# MCU_144_IOs.net
KiCad netlist of a schematic drawn in Altium Designer
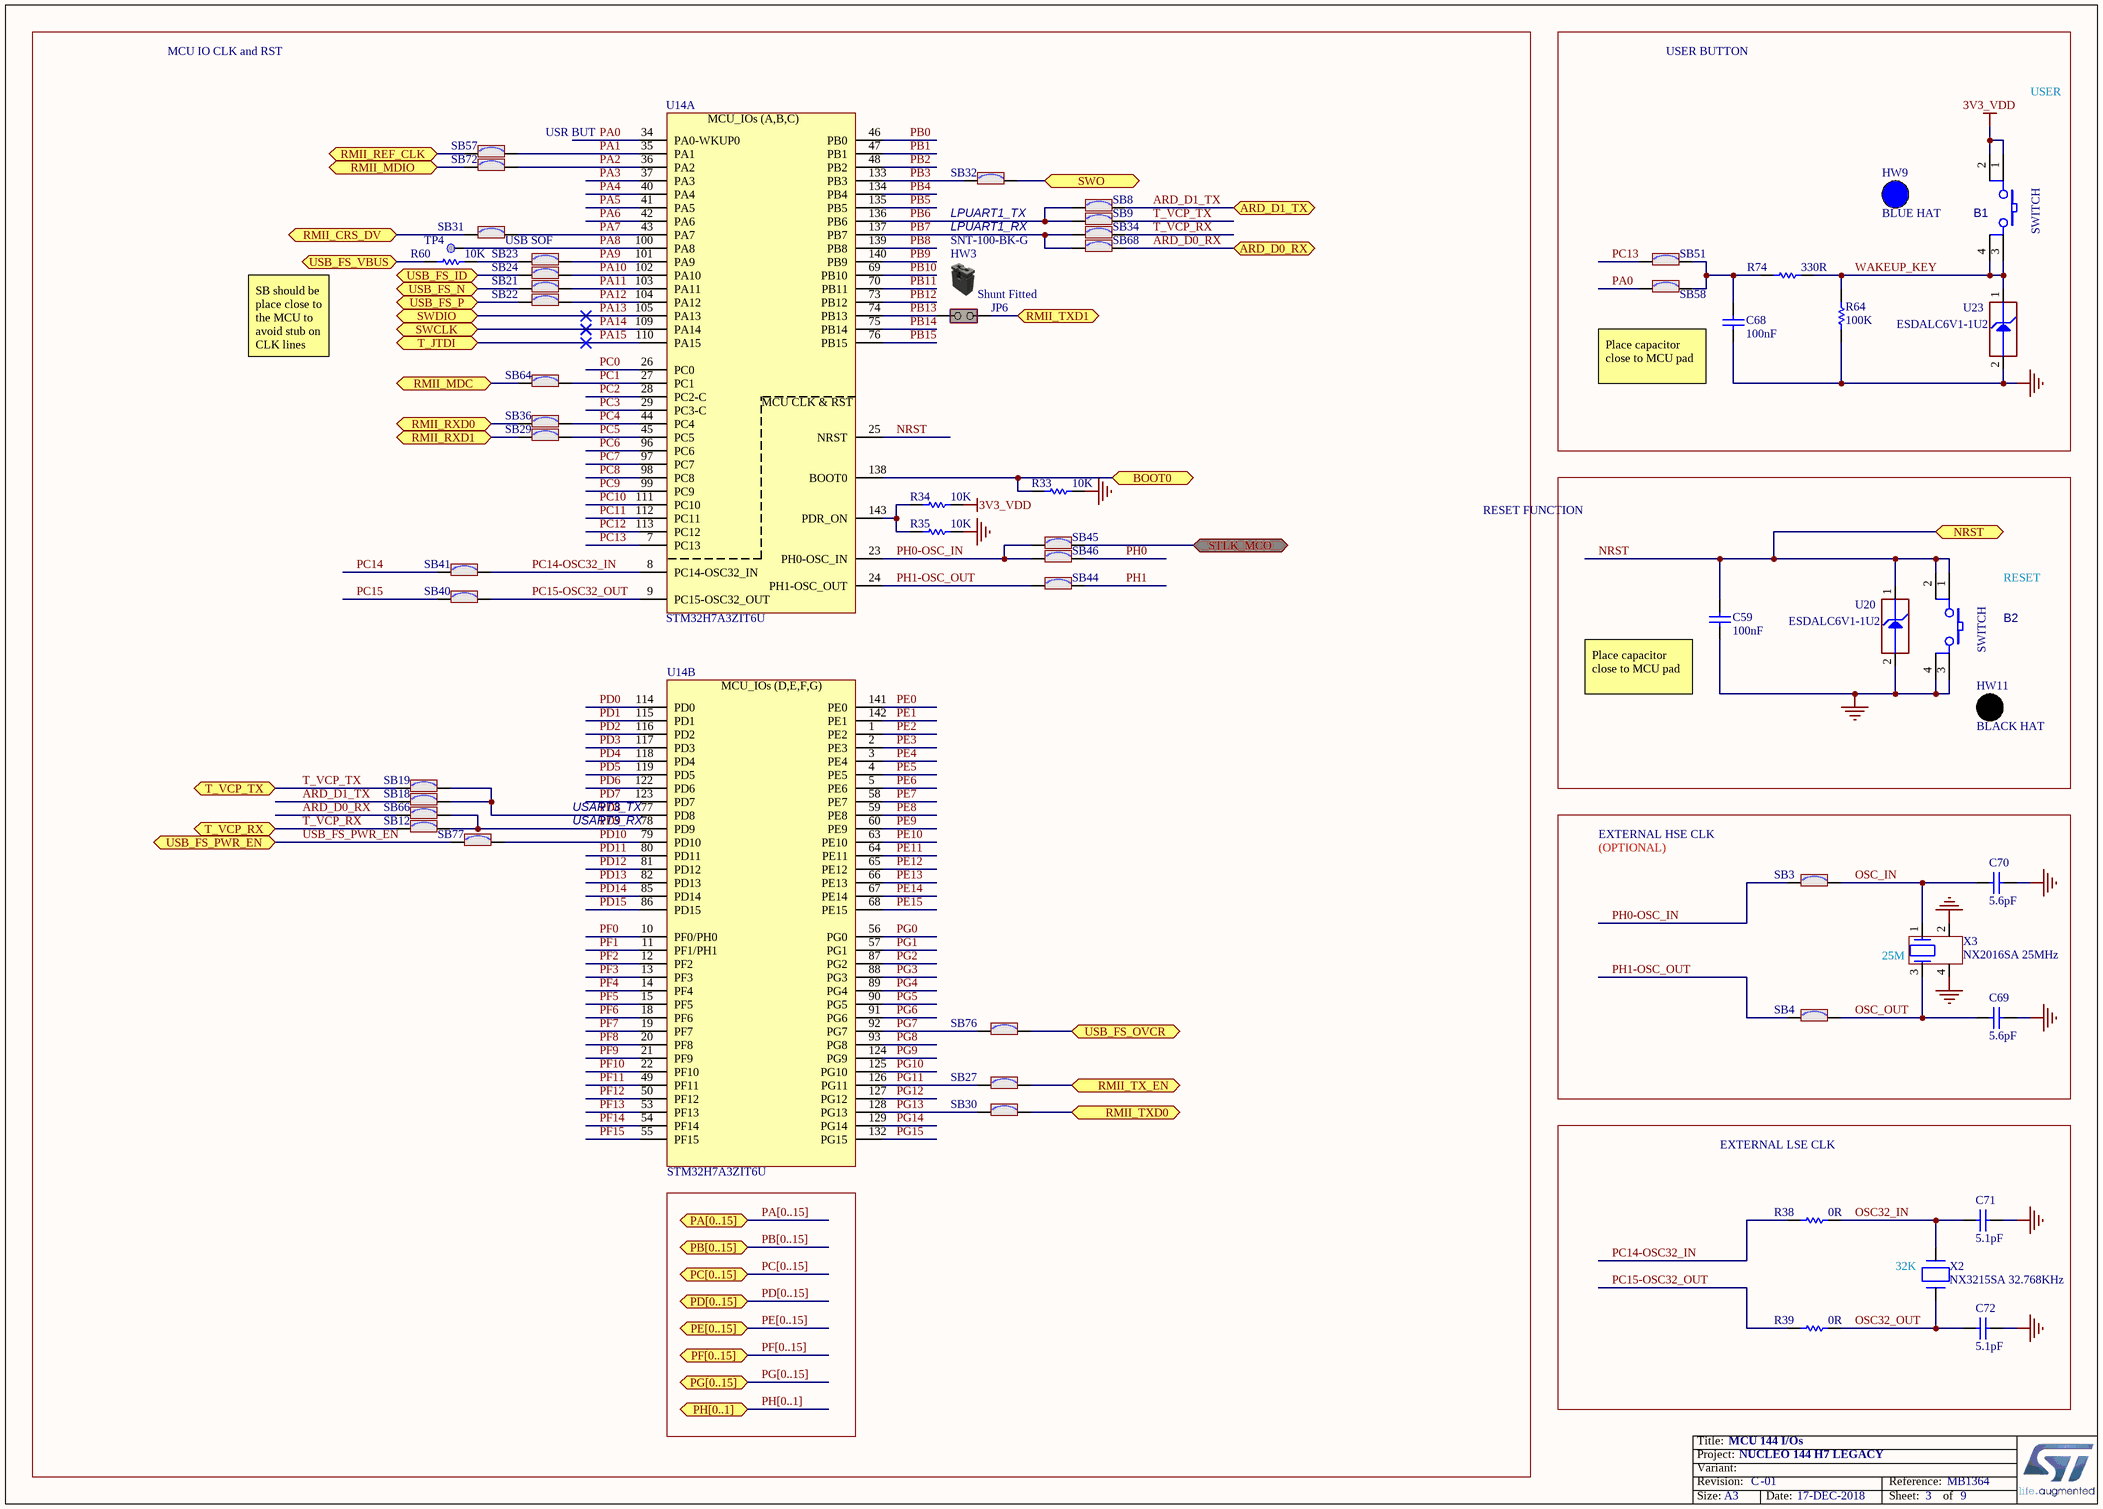
[diagram p0: MCU_144_IOs.SchDoc]

(export (version "E")
  (design (tool "Eeschema 10.0.6"))
  (components
    (comp (ref "B1")
      (value "SWITCH")
      (footprint "SWI_WEALTHMETAL_TD-0341_4P_BLUE")
      (description "Non-Open Push-Button 0.1A 24V")
      (fields
        (field (name "INTERNAL_PART_NUMBER") "MCD-00002")
        (field (name "MANUFACTURER_PART_NUMBER") "TD-0341")
        (field (name "PROVIDED_BY") "SUBCO")
      )
      (libsource (lib "MCD_PARTS_database") (part "SW-PUSH-CMS"))
    )
    (comp (ref "B2")
      (value "SWITCH")
      (footprint "SWI_WEALTHMETAL_TD-0341_4P_BLACK")
      (description "Non-Open Push-Button 0.1A 24V BLACK")
      (fields
        (field (name "INTERNAL_PART_NUMBER") "MCD-00001")
        (field (name "MANUFACTURER_PART_NUMBER") "TD-0341")
        (field (name "PROVIDED_BY") "SUBCO")
      )
      (libsource (lib "MCD_PARTS_database") (part "SW-PUSH-CMS"))
    )
    (comp (ref "C59")
      (value "100nF")
      (footprint "C0603")
      (description "Capacitor, MLCC, 100nF, 6V3, X5R, 10%, 0603, T=0,8mm")
      (fields
        (field (name "INTERNAL_PART_NUMBER") "MCD-00237")
        (field (name "MANUFACTURER_PART_NUMBER") "CC0603KRX5R5BB104")
        (field (name "PROVIDED_BY") "SUBCO")
      )
      (libsource (lib "MCD_PARTS_database") (part "Capacitor"))
    )
    (comp (ref "C68")
      (value "100nF")
      (footprint "C0603")
      (description "Capacitor, MLCC, 100nF, 6V3, X5R, 10%, 0603, T=0,8mm")
      (fields
        (field (name "INTERNAL_PART_NUMBER") "MCD-00237")
        (field (name "MANUFACTURER_PART_NUMBER") "CC0603KRX5R5BB104")
        (field (name "PROVIDED_BY") "SUBCO")
      )
      (libsource (lib "MCD_PARTS_database") (part "Capacitor"))
    )
    (comp (ref "C69")
      (value "5.6pF")
      (footprint "C0402")
      (description "Capacitor, MLCC, 5.6pF, 50V, NPO, 5%, 0402, T=0,5mm")
      (fields
        (field (name "INTERNAL_PART_NUMBER") "MCD-01374")
        (field (name "MANUFACTURER_PART_NUMBER") "CC0402BRNPO9BN5R6")
        (field (name "PROVIDED_BY") "SUBCO")
      )
      (libsource (lib "MCD_PARTS_database") (part "Capacitor"))
    )
    (comp (ref "C70")
      (value "5.6pF")
      (footprint "C0402")
      (description "Capacitor, MLCC, 5.6pF, 50V, NPO, 5%, 0402, T=0,5mm")
      (fields
        (field (name "INTERNAL_PART_NUMBER") "MCD-01374")
        (field (name "MANUFACTURER_PART_NUMBER") "CC0402BRNPO9BN5R6")
        (field (name "PROVIDED_BY") "SUBCO")
      )
      (libsource (lib "MCD_PARTS_database") (part "Capacitor"))
    )
    (comp (ref "C71")
      (value "5.1pF")
      (footprint "C0402")
      (description "Capacitor, MLCC, 5.1pF, 50V, NPO, +-0.25pF, 0402, T=0.5mm")
      (fields
        (field (name "INTERNAL_PART_NUMBER") "MCD-00003")
        (field (name "MANUFACTURER_PART_NUMBER") "CC0402CRNPO9BN5R1")
        (field (name "PROVIDED_BY") "SUBCO")
      )
      (libsource (lib "MCD_PARTS_database") (part "Capacitor"))
    )
    (comp (ref "C72")
      (value "5.1pF")
      (footprint "C0402")
      (description "Capacitor, MLCC, 5.1pF, 50V, NPO, +-0.25pF, 0402, T=0.5mm")
      (fields
        (field (name "INTERNAL_PART_NUMBER") "MCD-00003")
        (field (name "MANUFACTURER_PART_NUMBER") "CC0402CRNPO9BN5R1")
        (field (name "PROVIDED_BY") "SUBCO")
      )
      (libsource (lib "MCD_PARTS_database") (part "Capacitor"))
    )
    (comp (ref "HW3")
      (value "SNT-100-BK-G")
      (description "SHUNT 2.54mm BLACK")
      (fields
        (field (name "INTERNAL_PART_NUMBER") "MCD-00043")
        (field (name "MANUFACTURER") "SAMTEC")
        (field (name "PROVIDED_BY") "SUBCO")
      )
      (libsource (lib "MCD_PARTS_database") (part "Shunt Black 2.54mm"))
    )
    (comp (ref "HW9")
      (value "BLUE HAT")
      (description "Blue Hat for switch TD0341X-G01-BLU")
      (fields
        (field (name "INTERNAL_PART_NUMBER") "MCD-00634")
        (field (name "MANUFACTURER_PART_NUMBER") "988.16.09.3.00002_SH-517")
        (field (name "PROVIDED_BY") "SUBCO")
      )
      (libsource (lib "MCD_PARTS_database") (part "BUTTON_HAT_BLUE"))
    )
    (comp (ref "HW11")
      (value "BLACK HAT")
      (description "Black Hat for switch TD0341X-G01-BLA")
      (fields
        (field (name "INTERNAL_PART_NUMBER") "MCD-00635")
        (field (name "MANUFACTURER_PART_NUMBER") "988.16.09.3.00003_SH-517")
        (field (name "PROVIDED_BY") "SUBCO")
      )
      (libsource (lib "MCD_PARTS_database") (part "BUTTON_HAT_BLACK"))
    )
    (comp (ref "JP6")
      (value "Shunt Fitted")
      (footprint "CON_SAMTEC_TSW-102-07-G-S")
      (description "Header, 2x1, 2,54mm, VR, TH, Height 5.84mm/2.54mm - Shunt Fitted by default")
      (fields
        (field (name "INTERNAL_PART_NUMBER") "MCD-00683")
        (field (name "MANUFACTURER_PART_NUMBER") "TSW-102-07-x-S")
        (field (name "PROVIDED_BY") "SUBCO")
      )
      (libsource (lib "MCD_PARTS_database") (part "Jumper_Header 2x1 Fitted"))
    )
    (comp (ref "R33")
      (value "10K")
      (footprint "R0603")
      (description "Resistor,10K,0603,1%,1/10W")
      (fields
        (field (name "INTERNAL_PART_NUMBER") "MCD-00220")
        (field (name "MANUFACTURER_PART_NUMBER") "RC0603FR-0710KL")
        (field (name "PROVIDED_BY") "SUBCO")
      )
      (libsource (lib "MCD_PARTS_database") (part "Resistor"))
    )
    (comp (ref "R34")
      (value "10K")
      (footprint "R0603")
      (description "Resistor,10K,0603,1%,1/10W")
      (fields
        (field (name "INTERNAL_PART_NUMBER") "MCD-00220")
        (field (name "MANUFACTURER_PART_NUMBER") "RC0603FR-0710KL")
        (field (name "PROVIDED_BY") "SUBCO")
      )
      (libsource (lib "MCD_PARTS_database") (part "Resistor"))
    )
    (comp (ref "R35")
      (value "10K")
      (footprint "R0603")
      (description "Resistor,10K,0603,1%,1/10W")
      (fields
        (field (name "INTERNAL_PART_NUMBER") "MCD-00220")
        (field (name "MANUFACTURER_PART_NUMBER") "RC0603FR-0710KL")
        (field (name "PROVIDED_BY") "SUBCO")
      )
      (libsource (lib "MCD_PARTS_database") (part "Resistor"))
    )
    (comp (ref "R38")
      (value "0R")
      (footprint "R0603")
      (description "Resistor,0R,0603,5%,1/10W")
      (fields
        (field (name "INTERNAL_PART_NUMBER") "MCD-00056")
        (field (name "MANUFACTURER_PART_NUMBER") "RC0603JR-070RL")
        (field (name "PROVIDED_BY") "SUBCO")
      )
      (libsource (lib "MCD_PARTS_database") (part "Resistor"))
    )
    (comp (ref "R39")
      (value "0R")
      (footprint "R0603")
      (description "Resistor,0R,0603,5%,1/10W")
      (fields
        (field (name "INTERNAL_PART_NUMBER") "MCD-00056")
        (field (name "MANUFACTURER_PART_NUMBER") "RC0603JR-070RL")
        (field (name "PROVIDED_BY") "SUBCO")
      )
      (libsource (lib "MCD_PARTS_database") (part "Resistor"))
    )
    (comp (ref "R60")
      (value "10K")
      (footprint "R0402")
      (description "Resistor,10K,0402,1%,1/16W")
      (fields
        (field (name "INTERNAL_PART_NUMBER") "MCD-00053")
        (field (name "MANUFACTURER_PART_NUMBER") "RC0402FR-0710KL")
        (field (name "PROVIDED_BY") "SUBCO")
      )
      (libsource (lib "MCD_PARTS_database") (part "Resistor"))
    )
    (comp (ref "R64")
      (value "100K")
      (footprint "R0603")
      (description "Resistor,100K,0603,1%,1/10W")
      (fields
        (field (name "INTERNAL_PART_NUMBER") "MCD-00223")
        (field (name "MANUFACTURER_PART_NUMBER") "RC0603FR-07100KL")
        (field (name "PROVIDED_BY") "SUBCO")
      )
      (libsource (lib "MCD_PARTS_database") (part "Resistor"))
    )
    (comp (ref "R74")
      (value "330R")
      (footprint "R0603")
      (description "Resistor,330R,0603,1%,1/10W")
      (fields
        (field (name "INTERNAL_PART_NUMBER") "MCD-00197")
        (field (name "MANUFACTURER_PART_NUMBER") "RC0603FR-07330RL")
        (field (name "PROVIDED_BY") "SUBCO")
      )
      (libsource (lib "MCD_PARTS_database") (part "Resistor"))
    )
    (comp (ref "SB3")
      (value "SB_ON")
      (footprint "SOLDER-BRIDGE_R0603-0R")
      (description "Solder Bridge ON")
      (fields
        (field (name "INTERNAL_PART_NUMBER") "MCD-00071")
        (field (name "MANUFACTURER_PART_NUMBER") "RC0603JR-070RL")
        (field (name "PROVIDED_BY") "SUBCO")
      )
      (libsource (lib "MCD_PARTS_database") (part "SB_ON"))
    )
    (comp (ref "SB4")
      (value "SB_ON")
      (footprint "SOLDER-BRIDGE_R0603-0R")
      (description "Solder Bridge ON")
      (fields
        (field (name "INTERNAL_PART_NUMBER") "MCD-00071")
        (field (name "MANUFACTURER_PART_NUMBER") "RC0603JR-070RL")
        (field (name "PROVIDED_BY") "SUBCO")
      )
      (libsource (lib "MCD_PARTS_database") (part "SB_ON"))
    )
    (comp (ref "SB8")
      (value "SB_ON")
      (footprint "SOLDER-BRIDGE_R0603-0R")
      (description "Solder Bridge ON")
      (fields
        (field (name "INTERNAL_PART_NUMBER") "MCD-00071")
        (field (name "MANUFACTURER_PART_NUMBER") "RC0603JR-070RL")
        (field (name "PROVIDED_BY") "SUBCO")
      )
      (libsource (lib "") (part "SB_ON_1"))
    )
    (comp (ref "SB9")
      (value "SB_ON")
      (footprint "SOLDER-BRIDGE_R0603-0R")
      (description "Solder Bridge ON")
      (fields
        (field (name "INTERNAL_PART_NUMBER") "MCD-00071")
        (field (name "MANUFACTURER_PART_NUMBER") "RC0603JR-070RL")
        (field (name "PROVIDED_BY") "SUBCO")
      )
      (libsource (lib "") (part "SB_ON_1"))
    )
    (comp (ref "SB12")
      (value "SB_ON")
      (footprint "SOLDER-BRIDGE_R0603-0R")
      (description "Solder Bridge ON")
      (fields
        (field (name "INTERNAL_PART_NUMBER") "MCD-00071")
        (field (name "MANUFACTURER_PART_NUMBER") "RC0603JR-070RL")
        (field (name "PROVIDED_BY") "SUBCO")
      )
      (libsource (lib "") (part "SB_ON_1"))
    )
    (comp (ref "SB18")
      (value "SB_ON")
      (footprint "SOLDER-BRIDGE_R0603-0R")
      (description "Solder Bridge ON")
      (fields
        (field (name "INTERNAL_PART_NUMBER") "MCD-00071")
        (field (name "MANUFACTURER_PART_NUMBER") "RC0603JR-070RL")
        (field (name "PROVIDED_BY") "SUBCO")
      )
      (libsource (lib "") (part "SB_ON_1"))
    )
    (comp (ref "SB19")
      (value "SB_ON")
      (footprint "SOLDER-BRIDGE_R0603-0R")
      (description "Solder Bridge ON")
      (fields
        (field (name "INTERNAL_PART_NUMBER") "MCD-00071")
        (field (name "MANUFACTURER_PART_NUMBER") "RC0603JR-070RL")
        (field (name "PROVIDED_BY") "SUBCO")
      )
      (libsource (lib "") (part "SB_ON_1"))
    )
    (comp (ref "SB21")
      (value "SB_ON")
      (footprint "SOLDER-BRIDGE_R0603-0R")
      (description "Solder Bridge ON")
      (fields
        (field (name "INTERNAL_PART_NUMBER") "MCD-00071")
        (field (name "MANUFACTURER_PART_NUMBER") "RC0603JR-070RL")
        (field (name "PROVIDED_BY") "SUBCO")
      )
      (libsource (lib "") (part "SB_ON_1"))
    )
    (comp (ref "SB22")
      (value "SB_ON")
      (footprint "SOLDER-BRIDGE_R0603-0R")
      (description "Solder Bridge ON")
      (fields
        (field (name "INTERNAL_PART_NUMBER") "MCD-00071")
        (field (name "MANUFACTURER_PART_NUMBER") "RC0603JR-070RL")
        (field (name "PROVIDED_BY") "SUBCO")
      )
      (libsource (lib "") (part "SB_ON_1"))
    )
    (comp (ref "SB23")
      (value "SB_ON")
      (footprint "SOLDER-BRIDGE_R0603-0R")
      (description "Solder Bridge ON")
      (fields
        (field (name "INTERNAL_PART_NUMBER") "MCD-00071")
        (field (name "MANUFACTURER_PART_NUMBER") "RC0603JR-070RL")
        (field (name "PROVIDED_BY") "SUBCO")
      )
      (libsource (lib "") (part "SB_ON_1"))
    )
    (comp (ref "SB24")
      (value "SB_ON")
      (footprint "SOLDER-BRIDGE_R0603-0R")
      (description "Solder Bridge ON")
      (fields
        (field (name "INTERNAL_PART_NUMBER") "MCD-00071")
        (field (name "MANUFACTURER_PART_NUMBER") "RC0603JR-070RL")
        (field (name "PROVIDED_BY") "SUBCO")
      )
      (libsource (lib "") (part "SB_ON_1"))
    )
    (comp (ref "SB27")
      (value "SB_ON")
      (footprint "SOLDER-BRIDGE_R0603-0R")
      (description "Solder Bridge ON")
      (fields
        (field (name "INTERNAL_PART_NUMBER") "MCD-00071")
        (field (name "MANUFACTURER_PART_NUMBER") "RC0603JR-070RL")
        (field (name "PROVIDED_BY") "SUBCO")
      )
      (libsource (lib "") (part "SB_ON_1"))
    )
    (comp (ref "SB29")
      (value "SB_ON")
      (footprint "SOLDER-BRIDGE_R0603-0R")
      (description "Solder Bridge ON")
      (fields
        (field (name "INTERNAL_PART_NUMBER") "MCD-00071")
        (field (name "MANUFACTURER_PART_NUMBER") "RC0603JR-070RL")
        (field (name "PROVIDED_BY") "SUBCO")
      )
      (libsource (lib "MCD_PARTS_database") (part "SB_ON"))
    )
    (comp (ref "SB30")
      (value "SB_ON")
      (footprint "SOLDER-BRIDGE_R0603-0R")
      (description "Solder Bridge ON")
      (fields
        (field (name "INTERNAL_PART_NUMBER") "MCD-00071")
        (field (name "MANUFACTURER_PART_NUMBER") "RC0603JR-070RL")
        (field (name "PROVIDED_BY") "SUBCO")
      )
      (libsource (lib "") (part "SB_ON_1"))
    )
    (comp (ref "SB31")
      (value "SB_ON")
      (footprint "SOLDER-BRIDGE_R0603-0R")
      (description "Solder Bridge ON")
      (fields
        (field (name "INTERNAL_PART_NUMBER") "MCD-00071")
        (field (name "MANUFACTURER_PART_NUMBER") "RC0603JR-070RL")
        (field (name "PROVIDED_BY") "SUBCO")
      )
      (libsource (lib "") (part "SB_ON_1"))
    )
    (comp (ref "SB32")
      (value "SB_ON")
      (footprint "SOLDER-BRIDGE_R0603-0R")
      (description "Solder Bridge ON")
      (fields
        (field (name "INTERNAL_PART_NUMBER") "MCD-00071")
        (field (name "MANUFACTURER_PART_NUMBER") "RC0603JR-070RL")
        (field (name "PROVIDED_BY") "SUBCO")
      )
      (libsource (lib "") (part "SB_ON_1"))
    )
    (comp (ref "SB34")
      (value "SB_ON")
      (footprint "SOLDER-BRIDGE_R0603-0R")
      (description "Solder Bridge ON")
      (fields
        (field (name "INTERNAL_PART_NUMBER") "MCD-00071")
        (field (name "MANUFACTURER_PART_NUMBER") "RC0603JR-070RL")
        (field (name "PROVIDED_BY") "SUBCO")
      )
      (libsource (lib "") (part "SB_ON_1"))
    )
    (comp (ref "SB36")
      (value "SB_ON")
      (footprint "SOLDER-BRIDGE_R0603-0R")
      (description "Solder Bridge ON")
      (fields
        (field (name "INTERNAL_PART_NUMBER") "MCD-00071")
        (field (name "MANUFACTURER_PART_NUMBER") "RC0603JR-070RL")
        (field (name "PROVIDED_BY") "SUBCO")
      )
      (libsource (lib "MCD_PARTS_database") (part "SB_ON"))
    )
    (comp (ref "SB40")
      (value "SB_ON")
      (footprint "SOLDER-BRIDGE_R0603-0R")
      (description "Solder Bridge ON")
      (fields
        (field (name "INTERNAL_PART_NUMBER") "MCD-00071")
        (field (name "MANUFACTURER_PART_NUMBER") "RC0603JR-070RL")
        (field (name "PROVIDED_BY") "SUBCO")
      )
      (libsource (lib "MCD_PARTS_database") (part "SB_ON"))
    )
    (comp (ref "SB41")
      (value "SB_ON")
      (footprint "SOLDER-BRIDGE_R0603-0R")
      (description "Solder Bridge ON")
      (fields
        (field (name "INTERNAL_PART_NUMBER") "MCD-00071")
        (field (name "MANUFACTURER_PART_NUMBER") "RC0603JR-070RL")
        (field (name "PROVIDED_BY") "SUBCO")
      )
      (libsource (lib "MCD_PARTS_database") (part "SB_ON"))
    )
    (comp (ref "SB44")
      (value "SB_ON")
      (footprint "SOLDER-BRIDGE_R0603-0R")
      (description "Solder Bridge ON")
      (fields
        (field (name "INTERNAL_PART_NUMBER") "MCD-00071")
        (field (name "MANUFACTURER_PART_NUMBER") "RC0603JR-070RL")
        (field (name "PROVIDED_BY") "SUBCO")
      )
      (libsource (lib "MCD_PARTS_database") (part "SB_ON"))
    )
    (comp (ref "SB45")
      (value "SB_ON")
      (footprint "SOLDER-BRIDGE_R0603-0R")
      (description "Solder Bridge ON")
      (fields
        (field (name "INTERNAL_PART_NUMBER") "MCD-00071")
        (field (name "MANUFACTURER_PART_NUMBER") "RC0603JR-070RL")
        (field (name "PROVIDED_BY") "SUBCO")
      )
      (libsource (lib "MCD_PARTS_database") (part "SB_ON"))
    )
    (comp (ref "SB46")
      (value "SB_ON")
      (footprint "SOLDER-BRIDGE_R0603-0R")
      (description "Solder Bridge ON")
      (fields
        (field (name "INTERNAL_PART_NUMBER") "MCD-00071")
        (field (name "MANUFACTURER_PART_NUMBER") "RC0603JR-070RL")
        (field (name "PROVIDED_BY") "SUBCO")
      )
      (libsource (lib "MCD_PARTS_database") (part "SB_ON"))
    )
    (comp (ref "SB51")
      (value "SB_ON")
      (footprint "SOLDER-BRIDGE_R0603-0R")
      (description "Solder Bridge ON")
      (fields
        (field (name "INTERNAL_PART_NUMBER") "MCD-00071")
        (field (name "MANUFACTURER_PART_NUMBER") "RC0603JR-070RL")
        (field (name "PROVIDED_BY") "SUBCO")
      )
      (libsource (lib "") (part "SB_ON_1"))
    )
    (comp (ref "SB57")
      (value "SB_ON")
      (footprint "SOLDER-BRIDGE_R0603-0R")
      (description "Solder Bridge ON")
      (fields
        (field (name "INTERNAL_PART_NUMBER") "MCD-00071")
        (field (name "MANUFACTURER_PART_NUMBER") "RC0603JR-070RL")
        (field (name "PROVIDED_BY") "SUBCO")
      )
      (libsource (lib "") (part "SB_ON_1"))
    )
    (comp (ref "SB58")
      (value "SB_ON")
      (footprint "SOLDER-BRIDGE_R0603-0R")
      (description "Solder Bridge ON")
      (fields
        (field (name "INTERNAL_PART_NUMBER") "MCD-00071")
        (field (name "MANUFACTURER_PART_NUMBER") "RC0603JR-070RL")
        (field (name "PROVIDED_BY") "SUBCO")
      )
      (libsource (lib "") (part "SB_ON_1"))
    )
    (comp (ref "SB64")
      (value "SB_ON")
      (footprint "SOLDER-BRIDGE_R0603-0R")
      (description "Solder Bridge ON")
      (fields
        (field (name "INTERNAL_PART_NUMBER") "MCD-00071")
        (field (name "MANUFACTURER_PART_NUMBER") "RC0603JR-070RL")
        (field (name "PROVIDED_BY") "SUBCO")
      )
      (libsource (lib "MCD_PARTS_database") (part "SB_ON"))
    )
    (comp (ref "SB66")
      (value "SB_ON")
      (footprint "SOLDER-BRIDGE_R0402-0R")
      (description "Solder Bridge 0402 ON")
      (fields
        (field (name "INTERNAL_PART_NUMBER") "MCD-01618")
        (field (name "MANUFACTURER_PART_NUMBER") "RC0402JR-070RL")
        (field (name "PROVIDED_BY") "SUBCO")
      )
      (libsource (lib "MCD_PARTS_database") (part "SB_ON"))
    )
    (comp (ref "SB68")
      (value "SB_ON")
      (footprint "SOLDER-BRIDGE_R0402-0R")
      (description "Solder Bridge 0402 ON")
      (fields
        (field (name "INTERNAL_PART_NUMBER") "MCD-01618")
        (field (name "MANUFACTURER_PART_NUMBER") "RC0402JR-070RL")
        (field (name "PROVIDED_BY") "SUBCO")
      )
      (libsource (lib "MCD_PARTS_database") (part "SB_ON"))
    )
    (comp (ref "SB72")
      (value "SB_ON")
      (footprint "SOLDER-BRIDGE_R0603-0R")
      (description "Solder Bridge ON")
      (fields
        (field (name "INTERNAL_PART_NUMBER") "MCD-00071")
        (field (name "MANUFACTURER_PART_NUMBER") "RC0603JR-070RL")
        (field (name "PROVIDED_BY") "SUBCO")
      )
      (libsource (lib "") (part "SB_ON_1"))
    )
    (comp (ref "SB76")
      (value "SB_ON")
      (footprint "SOLDER-BRIDGE_R0603-0R")
      (description "Solder Bridge ON")
      (fields
        (field (name "INTERNAL_PART_NUMBER") "MCD-00071")
        (field (name "MANUFACTURER_PART_NUMBER") "RC0603JR-070RL")
        (field (name "PROVIDED_BY") "SUBCO")
      )
      (libsource (lib "") (part "SB_ON_1"))
    )
    (comp (ref "SB77")
      (value "SB_ON")
      (footprint "SOLDER-BRIDGE_R0603-0R")
      (description "Solder Bridge ON")
      (fields
        (field (name "INTERNAL_PART_NUMBER") "MCD-00071")
        (field (name "MANUFACTURER_PART_NUMBER") "RC0603JR-070RL")
        (field (name "PROVIDED_BY") "SUBCO")
      )
      (libsource (lib "") (part "SB_ON_1"))
    )
    (comp (ref "TP4")
      (value "Test Point")
      (footprint "TP_SMD_1MM")
      (description "Test Point 1mm")
      (fields
        (field (name "INTERNAL_PART_NUMBER") "MCD-00074")
        (field (name "MANUFACTURER_PART_NUMBER") "n/a")
      )
      (libsource (lib "MCD_PARTS_database") (part "Test Point"))
    )
    (comp (ref "U14")
      (value "STM32H7A3ZIT6U")
      (footprint "ICC_LQFP144_20X20_P050_SOCKET_YAMAICHI_IC149-144-145-B5_NM")
      (description "STM32H7A3ZIT6U, LQFP144 package, 20x20")
      (fields
        (field (name "INTERNAL_PART_NUMBER") "MCD-01349")
        (field (name "MANUFACTURER") "STMICROELECTRONICS")
        (field (name "PROVIDED_BY") "SUBCO with ST control")
      )
      (libsource (lib "MCD_PARTS_database") (part "STM32H7A3ZIT6"))
    )
    (comp (ref "U20")
      (value "ESDALC6V1-1U2")
      (footprint "ESD_ST0201")
      (description "ESD protection 6V1")
      (fields
        (field (name "INTERNAL_PART_NUMBER") "MCD-00170")
        (field (name "MANUFACTURER") "STMICROELECTRONICS")
        (field (name "PROVIDED_BY") "SUBCO with ST control")
      )
      (libsource (lib "MCD_PARTS_database") (part "ESD-TRANSIL"))
    )
    (comp (ref "U23")
      (value "ESDALC6V1-1U2")
      (footprint "ESD_ST0201")
      (description "ESD protection 6V1")
      (fields
        (field (name "INTERNAL_PART_NUMBER") "MCD-00170")
        (field (name "MANUFACTURER") "STMICROELECTRONICS")
        (field (name "PROVIDED_BY") "SUBCO with ST control")
      )
      (libsource (lib "MCD_PARTS_database") (part "ESD-TRANSIL"))
    )
    (comp (ref "X2")
      (value "NX3215SA 32.768KHz")
      (footprint "CRY_NX3215SA_2P")
      (description "Crystal 32.768kHz, 6pF, +-20ppm, 50Kohms max, SMD")
      (fields
        (field (name "INTERNAL_PART_NUMBER") "MCD-00091")
        (field (name "MANUFACTURER_PART_NUMBER") "NX3215SA 32.768KHz EXS00A-MU00525")
        (field (name "PROVIDED_BY") "SUBCO")
      )
      (libsource (lib "MCD_PARTS_database") (part "XTAL_2_PINS"))
    )
    (comp (ref "X3")
      (value "NX2016SA 25MHz")
      (footprint "CRY_NX2016SA_4P")
      (description "Crystal 25MHz, 6pF, +-20ppm, 80ohms max, SMD")
      (fields
        (field (name "INTERNAL_PART_NUMBER") "MCD-01364")
        (field (name "MANUFACTURER_PART_NUMBER") "NX2016SA 25MHz EXS00A-CS11321")
        (field (name "PROVIDED_BY") "SUBCO")
      )
      (libsource (lib "MCD_PARTS_database") (part "XTAL_4_PINS"))
    )
  )
  (nets
    (net (code "1") (name "/ARD_D0_RX") (class "Default")
      (node (ref "SB66") (pin "1") (pinfunction "1_1") (pintype "passive"))
      (node (ref "SB68") (pin "2") (pinfunction "2_2") (pintype "passive"))
    )
    (net (code "2") (name "/ARD_D1_TX") (class "Default")
      (node (ref "SB18") (pin "2") (pinfunction "2_2") (pintype "passive"))
      (node (ref "SB8") (pin "1") (pinfunction "1_1") (pintype "passive"))
    )
    (net (code "3") (name "/BOOT0") (class "Default")
      (node (ref "R33") (pin "1") (pinfunction "1_1") (pintype "passive"))
      (node (ref "U14") (pin "138") (pinfunction "BOOT0_138") (pintype "passive"))
    )
    (net (code "4") (name "/NRST") (class "Default")
      (node (ref "B2") (pin "1") (pinfunction "1_1") (pintype "passive"))
      (node (ref "B2") (pin "2") (pinfunction "2_2") (pintype "passive"))
      (node (ref "C59") (pin "2") (pinfunction "2_2") (pintype "passive"))
      (node (ref "U14") (pin "25") (pinfunction "NRST_25") (pintype "passive"))
      (node (ref "U20") (pin "1") (pinfunction "IO1_1") (pintype "passive"))
    )
    (net (code "5") (name "/OSC32_IN") (class "Default")
      (node (ref "C71") (pin "1") (pinfunction "1_1") (pintype "passive"))
      (node (ref "R38") (pin "2") (pinfunction "2_2") (pintype "passive"))
      (node (ref "X2") (pin "2") (pinfunction "X2_2") (pintype "passive"))
    )
    (net (code "6") (name "/OSC32_OUT") (class "Default")
      (node (ref "C72") (pin "1") (pinfunction "1_1") (pintype "passive"))
      (node (ref "R39") (pin "2") (pinfunction "2_2") (pintype "passive"))
      (node (ref "X2") (pin "1") (pinfunction "X1_1") (pintype "passive"))
    )
    (net (code "7") (name "/OSC_IN") (class "Default")
      (node (ref "C70") (pin "1") (pinfunction "1_1") (pintype "passive"))
      (node (ref "SB3") (pin "2") (pinfunction "2_2") (pintype "passive"))
      (node (ref "X3") (pin "1") (pinfunction "1_1") (pintype "passive"))
    )
    (net (code "8") (name "/OSC_OUT") (class "Default")
      (node (ref "C69") (pin "1") (pinfunction "1_1") (pintype "passive"))
      (node (ref "SB4") (pin "2") (pinfunction "2_2") (pintype "passive"))
      (node (ref "X3") (pin "3") (pinfunction "3_3") (pintype "passive"))
    )
    (net (code "9") (name "/PA0") (class "Default")
      (node (ref "SB58") (pin "2") (pinfunction "2_2") (pintype "passive"))
      (node (ref "U14") (pin "34") (pinfunction "PA0-WKUP0_34") (pintype "passive"))
    )
    (net (code "10") (name "/PA1") (class "Default")
      (node (ref "SB57") (pin "1") (pinfunction "1_1") (pintype "passive"))
      (node (ref "U14") (pin "35") (pinfunction "PA1_35") (pintype "passive"))
    )
    (net (code "11") (name "/PA2") (class "Default")
      (node (ref "SB72") (pin "1") (pinfunction "1_1") (pintype "passive"))
      (node (ref "U14") (pin "36") (pinfunction "PA2_36") (pintype "passive"))
    )
    (net (code "12") (name "/PA3") (class "Default")
      (node (ref "U14") (pin "37") (pinfunction "PA3_37") (pintype "passive"))
    )
    (net (code "13") (name "/PA4") (class "Default")
      (node (ref "U14") (pin "40") (pinfunction "PA4_40") (pintype "passive"))
    )
    (net (code "14") (name "/PA5") (class "Default")
      (node (ref "U14") (pin "41") (pinfunction "PA5_41") (pintype "passive"))
    )
    (net (code "15") (name "/PA6") (class "Default")
      (node (ref "U14") (pin "42") (pinfunction "PA6_42") (pintype "passive"))
    )
    (net (code "16") (name "/PA7") (class "Default")
      (node (ref "SB31") (pin "1") (pinfunction "1_1") (pintype "passive"))
      (node (ref "U14") (pin "43") (pinfunction "PA7_43") (pintype "passive"))
    )
    (net (code "17") (name "/PA8") (class "Default")
      (node (ref "TP4") (pin "1") (pinfunction "1_1") (pintype "passive"))
      (node (ref "U14") (pin "100") (pinfunction "PA8_100") (pintype "passive"))
    )
    (net (code "18") (name "/PA9") (class "Default")
      (node (ref "SB23") (pin "1") (pinfunction "1_1") (pintype "passive"))
      (node (ref "U14") (pin "101") (pinfunction "PA9_101") (pintype "passive"))
    )
    (net (code "19") (name "/PA10") (class "Default")
      (node (ref "SB24") (pin "1") (pinfunction "1_1") (pintype "passive"))
      (node (ref "U14") (pin "102") (pinfunction "PA10_102") (pintype "passive"))
    )
    (net (code "20") (name "/PA11") (class "Default")
      (node (ref "SB21") (pin "1") (pinfunction "1_1") (pintype "passive"))
      (node (ref "U14") (pin "103") (pinfunction "PA11_103") (pintype "passive"))
    )
    (net (code "21") (name "/PA12") (class "Default")
      (node (ref "SB22") (pin "1") (pinfunction "1_1") (pintype "passive"))
      (node (ref "U14") (pin "104") (pinfunction "PA12_104") (pintype "passive"))
    )
    (net (code "22") (name "/PA13") (class "Default")
      (node (ref "U14") (pin "105") (pinfunction "PA13_105") (pintype "passive"))
    )
    (net (code "23") (name "/PA14") (class "Default")
      (node (ref "U14") (pin "109") (pinfunction "PA14_109") (pintype "passive"))
    )
    (net (code "24") (name "/PA15") (class "Default")
      (node (ref "U14") (pin "110") (pinfunction "PA15_110") (pintype "passive"))
    )
    (net (code "26") (name "/PB0") (class "Default")
      (node (ref "U14") (pin "46") (pinfunction "PB0_46") (pintype "passive"))
    )
    (net (code "27") (name "/PB1") (class "Default")
      (node (ref "U14") (pin "47") (pinfunction "PB1_47") (pintype "passive"))
    )
    (net (code "28") (name "/PB2") (class "Default")
      (node (ref "U14") (pin "48") (pinfunction "PB2_48") (pintype "passive"))
    )
    (net (code "29") (name "/PB3") (class "Default")
      (node (ref "SB32") (pin "2") (pinfunction "2_2") (pintype "passive"))
      (node (ref "U14") (pin "133") (pinfunction "PB3_133") (pintype "passive"))
    )
    (net (code "30") (name "/PB4") (class "Default")
      (node (ref "U14") (pin "134") (pinfunction "PB4_134") (pintype "passive"))
    )
    (net (code "31") (name "/PB5") (class "Default")
      (node (ref "U14") (pin "135") (pinfunction "PB5_135") (pintype "passive"))
    )
    (net (code "32") (name "/PB6") (class "Default")
      (node (ref "SB8") (pin "2") (pinfunction "2_2") (pintype "passive"))
      (node (ref "SB9") (pin "2") (pinfunction "2_2") (pintype "passive"))
      (node (ref "U14") (pin "136") (pinfunction "PB6_136") (pintype "passive"))
    )
    (net (code "33") (name "/PB7") (class "Default")
      (node (ref "SB34") (pin "2") (pinfunction "2_2") (pintype "passive"))
      (node (ref "SB68") (pin "1") (pinfunction "1_1") (pintype "passive"))
      (node (ref "U14") (pin "137") (pinfunction "PB7_137") (pintype "passive"))
    )
    (net (code "34") (name "/PB8") (class "Default")
      (node (ref "U14") (pin "139") (pinfunction "PB8_139") (pintype "passive"))
    )
    (net (code "35") (name "/PB9") (class "Default")
      (node (ref "U14") (pin "140") (pinfunction "PB9_140") (pintype "passive"))
    )
    (net (code "36") (name "/PB10") (class "Default")
      (node (ref "U14") (pin "69") (pinfunction "PB10_69") (pintype "passive"))
    )
    (net (code "37") (name "/PB11") (class "Default")
      (node (ref "U14") (pin "70") (pinfunction "PB11_70") (pintype "passive"))
    )
    (net (code "38") (name "/PB12") (class "Default")
      (node (ref "U14") (pin "73") (pinfunction "PB12_73") (pintype "passive"))
    )
    (net (code "39") (name "/PB13") (class "Default")
      (node (ref "JP6") (pin "1") (pinfunction "COMMON_1") (pintype "passive"))
      (node (ref "U14") (pin "74") (pinfunction "PB13_74") (pintype "passive"))
    )
    (net (code "40") (name "/PB14") (class "Default")
      (node (ref "U14") (pin "75") (pinfunction "PB14_75") (pintype "passive"))
    )
    (net (code "41") (name "/PB15") (class "Default")
      (node (ref "U14") (pin "76") (pinfunction "PB15_76") (pintype "passive"))
    )
    (net (code "43") (name "/PC0") (class "Default")
      (node (ref "U14") (pin "26") (pinfunction "PC0_26") (pintype "passive"))
    )
    (net (code "44") (name "/PC1") (class "Default")
      (node (ref "SB64") (pin "2") (pinfunction "2_2") (pintype "passive"))
      (node (ref "U14") (pin "27") (pinfunction "PC1_27") (pintype "passive"))
    )
    (net (code "45") (name "/PC2") (class "Default")
      (node (ref "U14") (pin "28") (pinfunction "PC2-C_28") (pintype "passive"))
    )
    (net (code "46") (name "/PC3") (class "Default")
      (node (ref "U14") (pin "29") (pinfunction "PC3-C_29") (pintype "passive"))
    )
    (net (code "47") (name "/PC4") (class "Default")
      (node (ref "SB36") (pin "2") (pinfunction "2_2") (pintype "passive"))
      (node (ref "U14") (pin "44") (pinfunction "PC4_44") (pintype "passive"))
    )
    (net (code "48") (name "/PC5") (class "Default")
      (node (ref "SB29") (pin "2") (pinfunction "2_2") (pintype "passive"))
      (node (ref "U14") (pin "45") (pinfunction "PC5_45") (pintype "passive"))
    )
    (net (code "49") (name "/PC6") (class "Default")
      (node (ref "U14") (pin "96") (pinfunction "PC6_96") (pintype "passive"))
    )
    (net (code "50") (name "/PC7") (class "Default")
      (node (ref "U14") (pin "97") (pinfunction "PC7_97") (pintype "passive"))
    )
    (net (code "51") (name "/PC8") (class "Default")
      (node (ref "U14") (pin "98") (pinfunction "PC8_98") (pintype "passive"))
    )
    (net (code "52") (name "/PC9") (class "Default")
      (node (ref "U14") (pin "99") (pinfunction "PC9_99") (pintype "passive"))
    )
    (net (code "53") (name "/PC10") (class "Default")
      (node (ref "U14") (pin "111") (pinfunction "PC10_111") (pintype "passive"))
    )
    (net (code "54") (name "/PC11") (class "Default")
      (node (ref "U14") (pin "112") (pinfunction "PC11_112") (pintype "passive"))
    )
    (net (code "55") (name "/PC12") (class "Default")
      (node (ref "U14") (pin "113") (pinfunction "PC12_113") (pintype "passive"))
    )
    (net (code "56") (name "/PC13") (class "Default")
      (node (ref "SB51") (pin "2") (pinfunction "2_2") (pintype "passive"))
      (node (ref "U14") (pin "7") (pinfunction "PC13_7") (pintype "passive"))
    )
    (net (code "57") (name "/PC14") (class "Default")
      (node (ref "SB41") (pin "1") (pinfunction "1_1") (pintype "passive"))
    )
    (net (code "58") (name "/PC14-OSC32_IN") (class "Default")
      (node (ref "R38") (pin "1") (pinfunction "1_1") (pintype "passive"))
      (node (ref "SB41") (pin "2") (pinfunction "2_2") (pintype "passive"))
      (node (ref "U14") (pin "8") (pinfunction "PC14-OSC32_IN_8") (pintype "passive"))
    )
    (net (code "59") (name "/PC15") (class "Default")
      (node (ref "SB40") (pin "1") (pinfunction "1_1") (pintype "passive"))
    )
    (net (code "60") (name "/PC15-OSC32_OUT") (class "Default")
      (node (ref "R39") (pin "1") (pinfunction "1_1") (pintype "passive"))
      (node (ref "SB40") (pin "2") (pinfunction "2_2") (pintype "passive"))
      (node (ref "U14") (pin "9") (pinfunction "PC15-OSC32_OUT_9") (pintype "passive"))
    )
    (net (code "62") (name "/PD0") (class "Default")
      (node (ref "U14") (pin "114") (pinfunction "PD0_114") (pintype "passive"))
    )
    (net (code "63") (name "/PD1") (class "Default")
      (node (ref "U14") (pin "115") (pinfunction "PD1_115") (pintype "passive"))
    )
    (net (code "64") (name "/PD2") (class "Default")
      (node (ref "U14") (pin "116") (pinfunction "PD2_116") (pintype "passive"))
    )
    (net (code "65") (name "/PD3") (class "Default")
      (node (ref "U14") (pin "117") (pinfunction "PD3_117") (pintype "passive"))
    )
    (net (code "66") (name "/PD4") (class "Default")
      (node (ref "U14") (pin "118") (pinfunction "PD4_118") (pintype "passive"))
    )
    (net (code "67") (name "/PD5") (class "Default")
      (node (ref "U14") (pin "119") (pinfunction "PD5_119") (pintype "passive"))
    )
    (net (code "68") (name "/PD6") (class "Default")
      (node (ref "U14") (pin "122") (pinfunction "PD6_122") (pintype "passive"))
    )
    (net (code "69") (name "/PD7") (class "Default")
      (node (ref "U14") (pin "123") (pinfunction "PD7_123") (pintype "passive"))
    )
    (net (code "70") (name "/PD8") (class "Default")
      (node (ref "SB18") (pin "1") (pinfunction "1_1") (pintype "passive"))
      (node (ref "SB19") (pin "1") (pinfunction "1_1") (pintype "passive"))
      (node (ref "U14") (pin "77") (pinfunction "PD8_77") (pintype "passive"))
    )
    (net (code "71") (name "/PD9") (class "Default")
      (node (ref "SB12") (pin "1") (pinfunction "1_1") (pintype "passive"))
      (node (ref "SB66") (pin "2") (pinfunction "2_2") (pintype "passive"))
      (node (ref "U14") (pin "78") (pinfunction "PD9_78") (pintype "passive"))
    )
    (net (code "72") (name "/PD10") (class "Default")
      (node (ref "SB77") (pin "1") (pinfunction "1_1") (pintype "passive"))
      (node (ref "U14") (pin "79") (pinfunction "PD10_79") (pintype "passive"))
    )
    (net (code "73") (name "/PD11") (class "Default")
      (node (ref "U14") (pin "80") (pinfunction "PD11_80") (pintype "passive"))
    )
    (net (code "74") (name "/PD12") (class "Default")
      (node (ref "U14") (pin "81") (pinfunction "PD12_81") (pintype "passive"))
    )
    (net (code "75") (name "/PD13") (class "Default")
      (node (ref "U14") (pin "82") (pinfunction "PD13_82") (pintype "passive"))
    )
    (net (code "76") (name "/PD14") (class "Default")
      (node (ref "U14") (pin "85") (pinfunction "PD14_85") (pintype "passive"))
    )
    (net (code "77") (name "/PD15") (class "Default")
      (node (ref "U14") (pin "86") (pinfunction "PD15_86") (pintype "passive"))
    )
    (net (code "79") (name "/PE0") (class "Default")
      (node (ref "U14") (pin "141") (pinfunction "PE0_141") (pintype "passive"))
    )
    (net (code "80") (name "/PE1") (class "Default")
      (node (ref "U14") (pin "142") (pinfunction "PE1_142") (pintype "passive"))
    )
    (net (code "81") (name "/PE2") (class "Default")
      (node (ref "U14") (pin "1") (pinfunction "PE2_1") (pintype "passive"))
    )
    (net (code "82") (name "/PE3") (class "Default")
      (node (ref "U14") (pin "2") (pinfunction "PE3_2") (pintype "passive"))
    )
    (net (code "83") (name "/PE4") (class "Default")
      (node (ref "U14") (pin "3") (pinfunction "PE4_3") (pintype "passive"))
    )
    (net (code "84") (name "/PE5") (class "Default")
      (node (ref "U14") (pin "4") (pinfunction "PE5_4") (pintype "passive"))
    )
    (net (code "85") (name "/PE6") (class "Default")
      (node (ref "U14") (pin "5") (pinfunction "PE6_5") (pintype "passive"))
    )
    (net (code "86") (name "/PE7") (class "Default")
      (node (ref "U14") (pin "58") (pinfunction "PE7_58") (pintype "passive"))
    )
    (net (code "87") (name "/PE8") (class "Default")
      (node (ref "U14") (pin "59") (pinfunction "PE8_59") (pintype "passive"))
    )
    (net (code "88") (name "/PE9") (class "Default")
      (node (ref "U14") (pin "60") (pinfunction "PE9_60") (pintype "passive"))
    )
    (net (code "89") (name "/PE10") (class "Default")
      (node (ref "U14") (pin "63") (pinfunction "PE10_63") (pintype "passive"))
    )
    (net (code "90") (name "/PE11") (class "Default")
      (node (ref "U14") (pin "64") (pinfunction "PE11_64") (pintype "passive"))
    )
    (net (code "91") (name "/PE12") (class "Default")
      (node (ref "U14") (pin "65") (pinfunction "PE12_65") (pintype "passive"))
    )
    (net (code "92") (name "/PE13") (class "Default")
      (node (ref "U14") (pin "66") (pinfunction "PE13_66") (pintype "passive"))
    )
    (net (code "93") (name "/PE14") (class "Default")
      (node (ref "U14") (pin "67") (pinfunction "PE14_67") (pintype "passive"))
    )
    (net (code "94") (name "/PE15") (class "Default")
      (node (ref "U14") (pin "68") (pinfunction "PE15_68") (pintype "passive"))
    )
    (net (code "96") (name "/PF0") (class "Default")
      (node (ref "U14") (pin "10") (pinfunction "PF0/PH0_10") (pintype "passive"))
    )
    (net (code "97") (name "/PF1") (class "Default")
      (node (ref "U14") (pin "11") (pinfunction "PF1/PH1_11") (pintype "passive"))
    )
    (net (code "98") (name "/PF2") (class "Default")
      (node (ref "U14") (pin "12") (pinfunction "PF2_12") (pintype "passive"))
    )
    (net (code "99") (name "/PF3") (class "Default")
      (node (ref "U14") (pin "13") (pinfunction "PF3_13") (pintype "passive"))
    )
    (net (code "100") (name "/PF4") (class "Default")
      (node (ref "U14") (pin "14") (pinfunction "PF4_14") (pintype "passive"))
    )
    (net (code "101") (name "/PF5") (class "Default")
      (node (ref "U14") (pin "15") (pinfunction "PF5_15") (pintype "passive"))
    )
    (net (code "102") (name "/PF6") (class "Default")
      (node (ref "U14") (pin "18") (pinfunction "PF6_18") (pintype "passive"))
    )
    (net (code "103") (name "/PF7") (class "Default")
      (node (ref "U14") (pin "19") (pinfunction "PF7_19") (pintype "passive"))
    )
    (net (code "104") (name "/PF8") (class "Default")
      (node (ref "U14") (pin "20") (pinfunction "PF8_20") (pintype "passive"))
    )
    (net (code "105") (name "/PF9") (class "Default")
      (node (ref "U14") (pin "21") (pinfunction "PF9_21") (pintype "passive"))
    )
    (net (code "106") (name "/PF10") (class "Default")
      (node (ref "U14") (pin "22") (pinfunction "PF10_22") (pintype "passive"))
    )
    (net (code "107") (name "/PF11") (class "Default")
      (node (ref "U14") (pin "49") (pinfunction "PF11_49") (pintype "passive"))
    )
    (net (code "108") (name "/PF12") (class "Default")
      (node (ref "U14") (pin "50") (pinfunction "PF12_50") (pintype "passive"))
    )
    (net (code "109") (name "/PF13") (class "Default")
      (node (ref "U14") (pin "53") (pinfunction "PF13_53") (pintype "passive"))
    )
    (net (code "110") (name "/PF14") (class "Default")
      (node (ref "U14") (pin "54") (pinfunction "PF14_54") (pintype "passive"))
    )
    (net (code "111") (name "/PF15") (class "Default")
      (node (ref "U14") (pin "55") (pinfunction "PF15_55") (pintype "passive"))
    )
    (net (code "113") (name "/PG0") (class "Default")
      (node (ref "U14") (pin "56") (pinfunction "PG0_56") (pintype "passive"))
    )
    (net (code "114") (name "/PG1") (class "Default")
      (node (ref "U14") (pin "57") (pinfunction "PG1_57") (pintype "passive"))
    )
    (net (code "115") (name "/PG2") (class "Default")
      (node (ref "U14") (pin "87") (pinfunction "PG2_87") (pintype "passive"))
    )
    (net (code "116") (name "/PG3") (class "Default")
      (node (ref "U14") (pin "88") (pinfunction "PG3_88") (pintype "passive"))
    )
    (net (code "117") (name "/PG4") (class "Default")
      (node (ref "U14") (pin "89") (pinfunction "PG4_89") (pintype "passive"))
    )
    (net (code "118") (name "/PG5") (class "Default")
      (node (ref "U14") (pin "90") (pinfunction "PG5_90") (pintype "passive"))
    )
    (net (code "119") (name "/PG6") (class "Default")
      (node (ref "U14") (pin "91") (pinfunction "PG6_91") (pintype "passive"))
    )
    (net (code "120") (name "/PG7") (class "Default")
      (node (ref "SB76") (pin "2") (pinfunction "2_2") (pintype "passive"))
      (node (ref "U14") (pin "92") (pinfunction "PG7_92") (pintype "passive"))
    )
    (net (code "121") (name "/PG8") (class "Default")
      (node (ref "U14") (pin "93") (pinfunction "PG8_93") (pintype "passive"))
    )
    (net (code "122") (name "/PG9") (class "Default")
      (node (ref "U14") (pin "124") (pinfunction "PG9_124") (pintype "passive"))
    )
    (net (code "123") (name "/PG10") (class "Default")
      (node (ref "U14") (pin "125") (pinfunction "PG10_125") (pintype "passive"))
    )
    (net (code "124") (name "/PG11") (class "Default")
      (node (ref "SB27") (pin "2") (pinfunction "2_2") (pintype "passive"))
      (node (ref "U14") (pin "126") (pinfunction "PG11_126") (pintype "passive"))
    )
    (net (code "125") (name "/PG12") (class "Default")
      (node (ref "U14") (pin "127") (pinfunction "PG12_127") (pintype "passive"))
    )
    (net (code "126") (name "/PG13") (class "Default")
      (node (ref "SB30") (pin "2") (pinfunction "2_2") (pintype "passive"))
      (node (ref "U14") (pin "128") (pinfunction "PG13_128") (pintype "passive"))
    )
    (net (code "127") (name "/PG14") (class "Default")
      (node (ref "U14") (pin "129") (pinfunction "PG14_129") (pintype "passive"))
    )
    (net (code "128") (name "/PG15") (class "Default")
      (node (ref "U14") (pin "132") (pinfunction "PG15_132") (pintype "passive"))
    )
    (net (code "130") (name "/PH0") (class "Default")
      (node (ref "SB46") (pin "2") (pinfunction "2_2") (pintype "passive"))
    )
    (net (code "131") (name "/PH0-OSC_IN") (class "Default")
      (node (ref "SB3") (pin "1") (pinfunction "1_1") (pintype "passive"))
      (node (ref "SB45") (pin "1") (pinfunction "1_1") (pintype "passive"))
      (node (ref "SB46") (pin "1") (pinfunction "1_1") (pintype "passive"))
      (node (ref "U14") (pin "23") (pinfunction "PH0-OSC_IN_23") (pintype "passive"))
    )
    (net (code "132") (name "/PH1") (class "Default")
      (node (ref "SB44") (pin "2") (pinfunction "2_2") (pintype "passive"))
    )
    (net (code "133") (name "/PH1-OSC_OUT") (class "Default")
      (node (ref "SB4") (pin "1") (pinfunction "1_1") (pintype "passive"))
      (node (ref "SB44") (pin "1") (pinfunction "1_1") (pintype "passive"))
      (node (ref "U14") (pin "24") (pinfunction "PH1-OSC_OUT_24") (pintype "passive"))
    )
    (net (code "135") (name "/RMII_CRS_DV") (class "Default")
      (node (ref "SB31") (pin "2") (pinfunction "2_2") (pintype "passive"))
    )
    (net (code "136") (name "/RMII_MDC") (class "Default")
      (node (ref "SB64") (pin "1") (pinfunction "1_1") (pintype "passive"))
    )
    (net (code "137") (name "/RMII_MDIO") (class "Default")
      (node (ref "SB72") (pin "2") (pinfunction "2_2") (pintype "passive"))
    )
    (net (code "138") (name "/RMII_REF_CLK") (class "Default")
      (node (ref "SB57") (pin "2") (pinfunction "2_2") (pintype "passive"))
    )
    (net (code "139") (name "/RMII_RXD0") (class "Default")
      (node (ref "SB36") (pin "1") (pinfunction "1_1") (pintype "passive"))
    )
    (net (code "140") (name "/RMII_RXD1") (class "Default")
      (node (ref "SB29") (pin "1") (pinfunction "1_1") (pintype "passive"))
    )
    (net (code "141") (name "/RMII_TXD0") (class "Default")
      (node (ref "SB30") (pin "1") (pinfunction "1_1") (pintype "passive"))
    )
    (net (code "142") (name "/RMII_TXD1") (class "Default")
      (node (ref "JP6") (pin "2") (pinfunction "NO_2") (pintype "passive"))
    )
    (net (code "143") (name "/RMII_TX_EN") (class "Default")
      (node (ref "SB27") (pin "1") (pinfunction "1_1") (pintype "passive"))
    )
    (net (code "144") (name "/STLK_MCO") (class "Default")
      (node (ref "SB45") (pin "2") (pinfunction "2_2") (pintype "passive"))
    )
    (net (code "145") (name "/SWO") (class "Default")
      (node (ref "SB32") (pin "1") (pinfunction "1_1") (pintype "passive"))
    )
    (net (code "146") (name "/T_VCP_RX") (class "Default")
      (node (ref "SB12") (pin "2") (pinfunction "2_2") (pintype "passive"))
      (node (ref "SB34") (pin "1") (pinfunction "1_1") (pintype "passive"))
    )
    (net (code "147") (name "/T_VCP_TX") (class "Default")
      (node (ref "SB19") (pin "2") (pinfunction "2_2") (pintype "passive"))
      (node (ref "SB9") (pin "1") (pinfunction "1_1") (pintype "passive"))
    )
    (net (code "148") (name "/USB_FS_ID") (class "Default")
      (node (ref "SB24") (pin "2") (pinfunction "2_2") (pintype "passive"))
    )
    (net (code "149") (name "/USB_FS_N") (class "Default")
      (node (ref "SB21") (pin "2") (pinfunction "2_2") (pintype "passive"))
    )
    (net (code "150") (name "/USB_FS_OVCR") (class "Default")
      (node (ref "SB76") (pin "1") (pinfunction "1_1") (pintype "passive"))
    )
    (net (code "151") (name "/USB_FS_P") (class "Default")
      (node (ref "SB22") (pin "2") (pinfunction "2_2") (pintype "passive"))
    )
    (net (code "152") (name "/USB_FS_PWR_EN") (class "Default")
      (node (ref "SB77") (pin "2") (pinfunction "2_2") (pintype "passive"))
    )
    (net (code "153") (name "/USB_FS_VBUS") (class "Default")
      (node (ref "R60") (pin "1") (pinfunction "1_1") (pintype "passive"))
    )
    (net (code "154") (name "/WAKEUP_KEY") (class "Default")
      (node (ref "B1") (pin "3") (pinfunction "3_3") (pintype "passive"))
      (node (ref "B1") (pin "4") (pinfunction "4_4") (pintype "passive"))
      (node (ref "R64") (pin "2") (pinfunction "2_2") (pintype "passive"))
      (node (ref "R74") (pin "2") (pinfunction "2_2") (pintype "passive"))
      (node (ref "U23") (pin "1") (pinfunction "IO1_1") (pintype "passive"))
    )
    (net (code "155") (name "3V3_VDD") (class "Default")
      (node (ref "B1") (pin "1") (pinfunction "1_1") (pintype "passive"))
      (node (ref "B1") (pin "2") (pinfunction "2_2") (pintype "passive"))
      (node (ref "R34") (pin "2") (pinfunction "2_2") (pintype "passive"))
    )
    (net (code "156") (name "GND") (class "Default")
      (node (ref "B2") (pin "3") (pinfunction "3_3") (pintype "passive"))
      (node (ref "B2") (pin "4") (pinfunction "4_4") (pintype "passive"))
      (node (ref "C59") (pin "1") (pinfunction "1_1") (pintype "passive"))
      (node (ref "C68") (pin "1") (pinfunction "1_1") (pintype "passive"))
      (node (ref "C69") (pin "2") (pinfunction "2_2") (pintype "passive"))
      (node (ref "C70") (pin "2") (pinfunction "2_2") (pintype "passive"))
      (node (ref "C71") (pin "2") (pinfunction "2_2") (pintype "passive"))
      (node (ref "C72") (pin "2") (pinfunction "2_2") (pintype "passive"))
      (node (ref "R33") (pin "2") (pinfunction "2_2") (pintype "passive"))
      (node (ref "R35") (pin "2") (pinfunction "2_2") (pintype "passive"))
      (node (ref "R64") (pin "1") (pinfunction "1_1") (pintype "passive"))
      (node (ref "U20") (pin "2") (pinfunction "GND_2") (pintype "passive"))
      (node (ref "U23") (pin "2") (pinfunction "GND_2") (pintype "passive"))
      (node (ref "X3") (pin "2") (pinfunction "2_2") (pintype "passive"))
      (node (ref "X3") (pin "4") (pinfunction "4_4") (pintype "passive"))
    )
    (net (code "157") (name "Net-(C68-Pad2)") (class "Default")
      (node (ref "C68") (pin "2") (pinfunction "2_2") (pintype "passive"))
      (node (ref "R74") (pin "1") (pinfunction "1_1") (pintype "passive"))
      (node (ref "SB51") (pin "1") (pinfunction "1_1") (pintype "passive"))
      (node (ref "SB58") (pin "1") (pinfunction "1_1") (pintype "passive"))
    )
    (net (code "158") (name "Net-(R60-Pad2)") (class "Default")
      (node (ref "R60") (pin "2") (pinfunction "2_2") (pintype "passive"))
      (node (ref "SB23") (pin "2") (pinfunction "2_2") (pintype "passive"))
    )
    (net (code "159") (name "Net-(U14A-PDR_ON)") (class "Default")
      (node (ref "R34") (pin "1") (pinfunction "1_1") (pintype "passive"))
      (node (ref "R35") (pin "1") (pinfunction "1_1") (pintype "passive"))
      (node (ref "U14") (pin "143") (pinfunction "PDR_ON_143") (pintype "passive"))
    )
  )
)
